# GSG_RX.net
KiCad netlist of a schematic drawn in Altium Designer
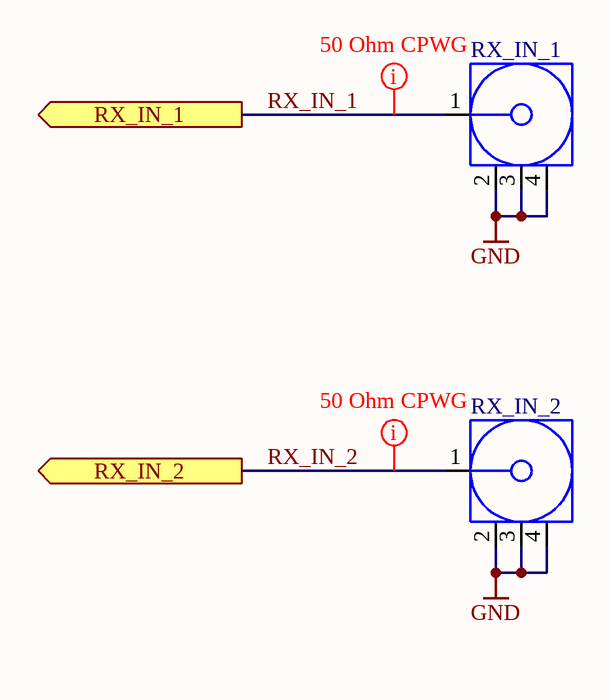
[diagram p0: GSG_RX.SchDoc]

(export (version "E")
  (design (tool "Eeschema 10.0.6"))
  (components
    (comp (ref "RX_IN_1")
      (value "60312862112552")
      (footprint "60312862112552")
      (description "WR-SMA Connector, PCB Solderless, DC~18GHz, 50Ohm")
      (fields (field (name "MANUFACTURER") "Würth"))
      (libsource (lib "database_library") (part "60312862112552"))
    )
    (comp (ref "RX_IN_2")
      (value "60312862112552")
      (footprint "60312862112552")
      (description "WR-SMA Connector, PCB Solderless, DC~18GHz, 50Ohm")
      (fields (field (name "MANUFACTURER") "Würth"))
      (libsource (lib "database_library") (part "60312862112552"))
    )
  )
  (nets
    (net (code "1") (name "/RX_IN_1") (class "Default")
      (node (ref "RX_IN_1") (pin "1") (pinfunction "Signal_1") (pintype "passive"))
    )
    (net (code "2") (name "/RX_IN_2") (class "Default")
      (node (ref "RX_IN_2") (pin "1") (pinfunction "Signal_1") (pintype "passive"))
    )
    (net (code "3") (name "GND") (class "Default")
      (node (ref "RX_IN_1") (pin "2") (pinfunction "GND_2") (pintype "passive"))
      (node (ref "RX_IN_1") (pin "3") (pinfunction "GND_3") (pintype "passive"))
      (node (ref "RX_IN_1") (pin "4") (pinfunction "GND_4") (pintype "passive"))
      (node (ref "RX_IN_2") (pin "2") (pinfunction "GND_2") (pintype "passive"))
      (node (ref "RX_IN_2") (pin "3") (pinfunction "GND_3") (pintype "passive"))
      (node (ref "RX_IN_2") (pin "4") (pinfunction "GND_4") (pintype "passive"))
    )
  )
)
